# DRV.net
KiCad netlist of a schematic drawn in Altium Designer
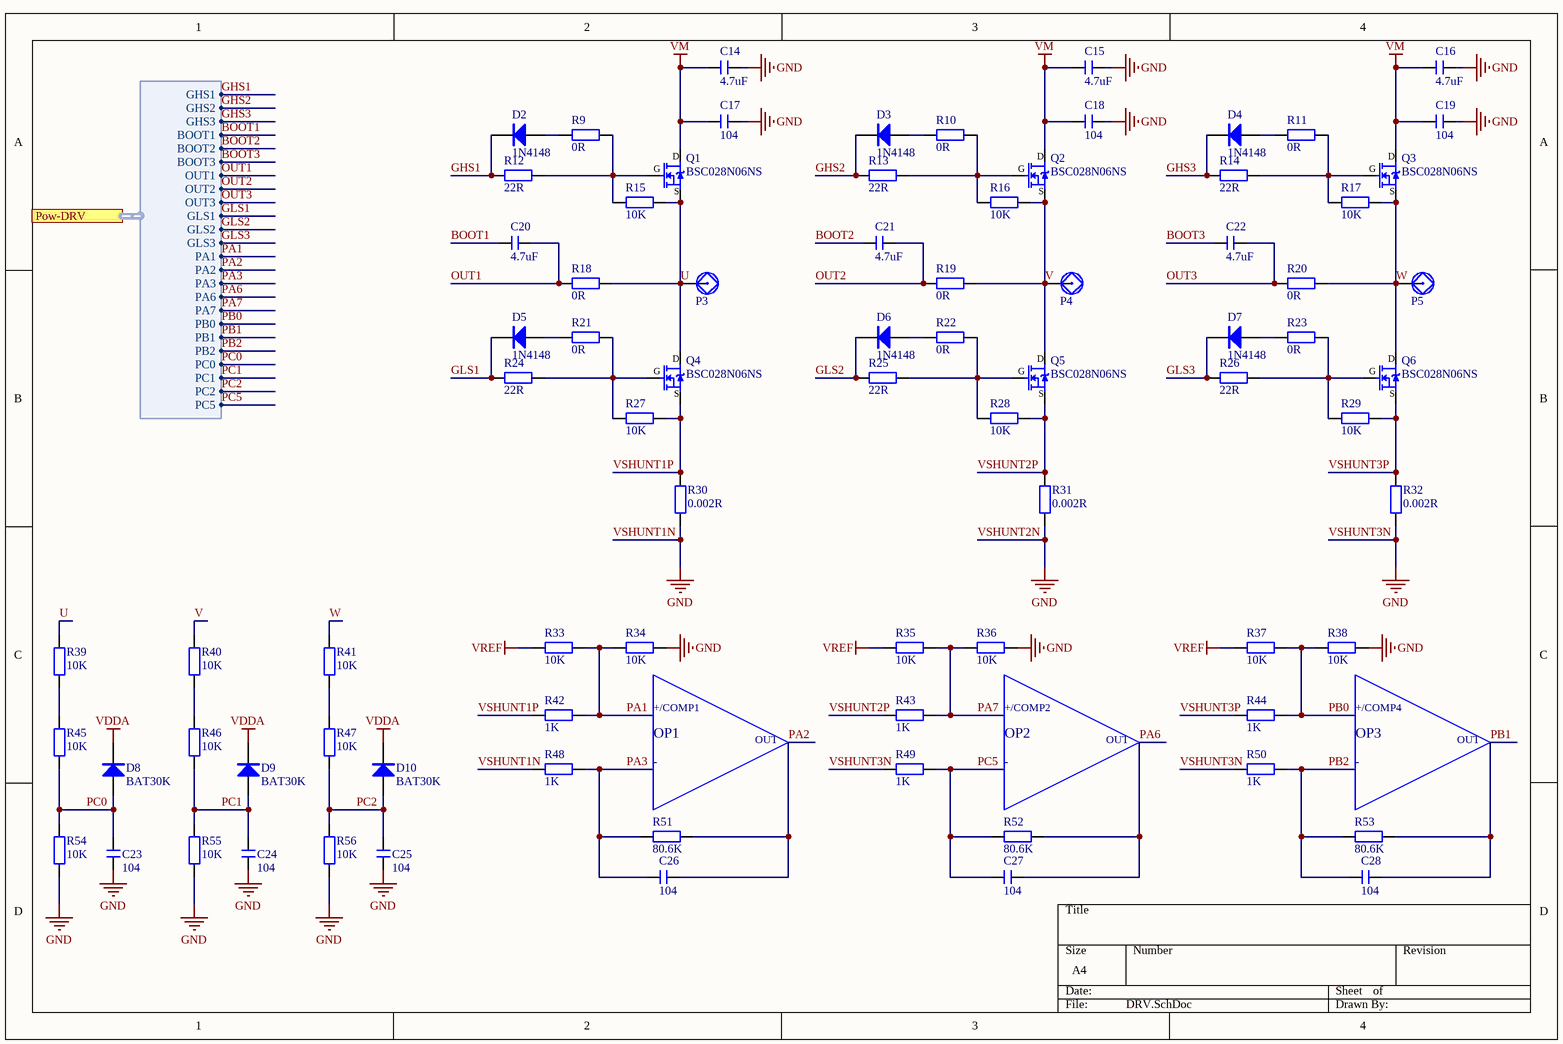
[diagram p0: DRV.SchDoc]

(export (version "E")
  (design (tool "Eeschema 10.0.6"))
  (components
    (comp (ref "C14")
      (value "4.7uF")
      (footprint "C 1206_L")
      (description "无极性贴片电容")
      (fields (field (name "版权归属") "源创客"))
      (libsource (lib "3.1   - 电阻-电容-电感") (part "C"))
    )
    (comp (ref "C15")
      (value "4.7uF")
      (footprint "C 1206_L")
      (description "无极性贴片电容")
      (fields (field (name "版权归属") "源创客"))
      (libsource (lib "3.1   - 电阻-电容-电感") (part "C"))
    )
    (comp (ref "C16")
      (value "4.7uF")
      (footprint "C 1206_L")
      (description "无极性贴片电容")
      (fields (field (name "版权归属") "源创客"))
      (libsource (lib "3.1   - 电阻-电容-电感") (part "C"))
    )
    (comp (ref "C17")
      (value "104")
      (footprint "C 0603_L")
      (description "无极性贴片电容")
      (fields (field (name "版权归属") "源创客"))
      (libsource (lib "3.1   - 电阻-电容-电感") (part "C"))
    )
    (comp (ref "C18")
      (value "104")
      (footprint "C 0603_L")
      (description "无极性贴片电容")
      (fields (field (name "版权归属") "源创客"))
      (libsource (lib "3.1   - 电阻-电容-电感") (part "C"))
    )
    (comp (ref "C19")
      (value "104")
      (footprint "C 0603_L")
      (description "无极性贴片电容")
      (fields (field (name "版权归属") "源创客"))
      (libsource (lib "3.1   - 电阻-电容-电感") (part "C"))
    )
    (comp (ref "C20")
      (value "4.7uF")
      (footprint "C 0805_L")
      (description "无极性贴片电容")
      (fields (field (name "版权归属") "源创客"))
      (libsource (lib "3.1   - 电阻-电容-电感") (part "C"))
    )
    (comp (ref "C21")
      (value "4.7uF")
      (footprint "C 0805_L")
      (description "无极性贴片电容")
      (fields (field (name "版权归属") "源创客"))
      (libsource (lib "3.1   - 电阻-电容-电感") (part "C"))
    )
    (comp (ref "C22")
      (value "4.7uF")
      (footprint "C 0805_L")
      (description "无极性贴片电容")
      (fields (field (name "版权归属") "源创客"))
      (libsource (lib "3.1   - 电阻-电容-电感") (part "C"))
    )
    (comp (ref "C23")
      (value "104")
      (footprint "C 0603_L")
      (description "无极性贴片电容")
      (fields (field (name "版权归属") "源创客"))
      (libsource (lib "3.1   - 电阻-电容-电感") (part "C"))
    )
    (comp (ref "C24")
      (value "104")
      (footprint "C 0603_L")
      (description "无极性贴片电容")
      (fields (field (name "版权归属") "源创客"))
      (libsource (lib "3.1   - 电阻-电容-电感") (part "C"))
    )
    (comp (ref "C25")
      (value "104")
      (footprint "C 0603_L")
      (description "无极性贴片电容")
      (fields (field (name "版权归属") "源创客"))
      (libsource (lib "3.1   - 电阻-电容-电感") (part "C"))
    )
    (comp (ref "C26")
      (value "104")
      (footprint "C 0603_L")
      (description "无极性贴片电容")
      (fields (field (name "版权归属") "源创客"))
      (libsource (lib "3.1   - 电阻-电容-电感") (part "C"))
    )
    (comp (ref "C27")
      (value "104")
      (footprint "C 0603_L")
      (description "无极性贴片电容")
      (fields (field (name "版权归属") "源创客"))
      (libsource (lib "3.1   - 电阻-电容-电感") (part "C"))
    )
    (comp (ref "C28")
      (value "104")
      (footprint "C 0603_L")
      (description "无极性贴片电容")
      (fields (field (name "版权归属") "源创客"))
      (libsource (lib "3.1   - 电阻-电容-电感") (part "C"))
    )
    (comp (ref "D2")
      (value "1N4148")
      (footprint "SOD-323")
      (description "高速开关二极管")
      (fields (field (name "版权归属") "源创客"))
      (libsource (lib "8.1   - 二极管-整流桥") (part "1N4148"))
    )
    (comp (ref "D3")
      (value "1N4148")
      (footprint "SOD-323")
      (description "高速开关二极管")
      (fields (field (name "版权归属") "源创客"))
      (libsource (lib "8.1   - 二极管-整流桥") (part "1N4148"))
    )
    (comp (ref "D4")
      (value "1N4148")
      (footprint "SOD-323")
      (description "高速开关二极管")
      (fields (field (name "版权归属") "源创客"))
      (libsource (lib "8.1   - 二极管-整流桥") (part "1N4148"))
    )
    (comp (ref "D5")
      (value "1N4148")
      (footprint "SOD-323")
      (description "高速开关二极管")
      (fields (field (name "版权归属") "源创客"))
      (libsource (lib "8.1   - 二极管-整流桥") (part "1N4148"))
    )
    (comp (ref "D6")
      (value "1N4148")
      (footprint "SOD-323")
      (description "高速开关二极管")
      (fields (field (name "版权归属") "源创客"))
      (libsource (lib "8.1   - 二极管-整流桥") (part "1N4148"))
    )
    (comp (ref "D7")
      (value "1N4148")
      (footprint "SOD-323")
      (description "高速开关二极管")
      (fields (field (name "版权归属") "源创客"))
      (libsource (lib "8.1   - 二极管-整流桥") (part "1N4148"))
    )
    (comp (ref "D8")
      (value "BAT30K")
      (footprint "SOD-523")
      (description "肖特基二极管")
      (fields (field (name "版权归属") "源创客"))
      (libsource (lib "8.1   - 二极管-整流桥") (part "SS14"))
    )
    (comp (ref "D9")
      (value "BAT30K")
      (footprint "SOD-523")
      (description "肖特基二极管")
      (fields (field (name "版权归属") "源创客"))
      (libsource (lib "8.1   - 二极管-整流桥") (part "SS14"))
    )
    (comp (ref "D10")
      (value "BAT30K")
      (footprint "SOD-523")
      (description "肖特基二极管")
      (fields (field (name "版权归属") "源创客"))
      (libsource (lib "8.1   - 二极管-整流桥") (part "SS14"))
    )
    (comp (ref "P3")
      (value "功率焊盘")
      (footprint "功率焊盘")
      (libsource (lib "STSPIN32G4-Test-board") (part "功率焊盘"))
    )
    (comp (ref "P4")
      (value "功率焊盘")
      (footprint "功率焊盘")
      (libsource (lib "STSPIN32G4-Test-board") (part "功率焊盘"))
    )
    (comp (ref "P5")
      (value "功率焊盘")
      (footprint "功率焊盘")
      (libsource (lib "STSPIN32G4-Test-board") (part "功率焊盘"))
    )
    (comp (ref "Q1")
      (value "BSC028N06NS")
      (footprint "BSC028N06NS")
      (description "N沟场，60V/100A")
      (fields (field (name "版权归属") "源创客"))
      (libsource (lib "STSPIN32G4-Test-board") (part "BSC028N06NS"))
    )
    (comp (ref "Q2")
      (value "BSC028N06NS")
      (footprint "BSC028N06NS")
      (description "N沟场，60V/100A")
      (fields (field (name "版权归属") "源创客"))
      (libsource (lib "STSPIN32G4-Test-board") (part "BSC028N06NS"))
    )
    (comp (ref "Q3")
      (value "BSC028N06NS")
      (footprint "BSC028N06NS")
      (description "N沟场，60V/100A")
      (fields (field (name "版权归属") "源创客"))
      (libsource (lib "STSPIN32G4-Test-board") (part "BSC028N06NS"))
    )
    (comp (ref "Q4")
      (value "BSC028N06NS")
      (footprint "BSC028N06NS")
      (description "N沟场，60V/100A")
      (fields (field (name "版权归属") "源创客"))
      (libsource (lib "STSPIN32G4-Test-board") (part "BSC028N06NS"))
    )
    (comp (ref "Q5")
      (value "BSC028N06NS")
      (footprint "BSC028N06NS")
      (description "N沟场，60V/100A")
      (fields (field (name "版权归属") "源创客"))
      (libsource (lib "STSPIN32G4-Test-board") (part "BSC028N06NS"))
    )
    (comp (ref "Q6")
      (value "BSC028N06NS")
      (footprint "BSC028N06NS")
      (description "N沟场，60V/100A")
      (fields (field (name "版权归属") "源创客"))
      (libsource (lib "STSPIN32G4-Test-board") (part "BSC028N06NS"))
    )
    (comp (ref "R9")
      (value "0R")
      (footprint "R 0603_L")
      (description "贴片电阻")
      (fields (field (name "版权归属") "源创客"))
      (libsource (lib "3.1   - 电阻-电容-电感") (part "R"))
    )
    (comp (ref "R10")
      (value "0R")
      (footprint "R 0603_L")
      (description "贴片电阻")
      (fields (field (name "版权归属") "源创客"))
      (libsource (lib "3.1   - 电阻-电容-电感") (part "R"))
    )
    (comp (ref "R11")
      (value "0R")
      (footprint "R 0603_L")
      (description "贴片电阻")
      (fields (field (name "版权归属") "源创客"))
      (libsource (lib "3.1   - 电阻-电容-电感") (part "R"))
    )
    (comp (ref "R12")
      (value "22R")
      (footprint "R 0603_L")
      (description "贴片电阻")
      (fields (field (name "版权归属") "源创客"))
      (libsource (lib "3.1   - 电阻-电容-电感") (part "R"))
    )
    (comp (ref "R13")
      (value "22R")
      (footprint "R 0603_L")
      (description "贴片电阻")
      (fields (field (name "版权归属") "源创客"))
      (libsource (lib "3.1   - 电阻-电容-电感") (part "R"))
    )
    (comp (ref "R14")
      (value "22R")
      (footprint "R 0603_L")
      (description "贴片电阻")
      (fields (field (name "版权归属") "源创客"))
      (libsource (lib "3.1   - 电阻-电容-电感") (part "R"))
    )
    (comp (ref "R15")
      (value "10K")
      (footprint "R 0603_L")
      (description "贴片电阻")
      (fields (field (name "版权归属") "源创客"))
      (libsource (lib "3.1   - 电阻-电容-电感") (part "R"))
    )
    (comp (ref "R16")
      (value "10K")
      (footprint "R 0603_L")
      (description "贴片电阻")
      (fields (field (name "版权归属") "源创客"))
      (libsource (lib "3.1   - 电阻-电容-电感") (part "R"))
    )
    (comp (ref "R17")
      (value "10K")
      (footprint "R 0603_L")
      (description "贴片电阻")
      (fields (field (name "版权归属") "源创客"))
      (libsource (lib "3.1   - 电阻-电容-电感") (part "R"))
    )
    (comp (ref "R18")
      (value "0R")
      (footprint "R 0603_L")
      (description "贴片电阻")
      (fields (field (name "版权归属") "源创客"))
      (libsource (lib "3.1   - 电阻-电容-电感") (part "R"))
    )
    (comp (ref "R19")
      (value "0R")
      (footprint "R 0603_L")
      (description "贴片电阻")
      (fields (field (name "版权归属") "源创客"))
      (libsource (lib "3.1   - 电阻-电容-电感") (part "R"))
    )
    (comp (ref "R20")
      (value "0R")
      (footprint "R 0603_L")
      (description "贴片电阻")
      (fields (field (name "版权归属") "源创客"))
      (libsource (lib "3.1   - 电阻-电容-电感") (part "R"))
    )
    (comp (ref "R21")
      (value "0R")
      (footprint "R 0603_L")
      (description "贴片电阻")
      (fields (field (name "版权归属") "源创客"))
      (libsource (lib "3.1   - 电阻-电容-电感") (part "R"))
    )
    (comp (ref "R22")
      (value "0R")
      (footprint "R 0603_L")
      (description "贴片电阻")
      (fields (field (name "版权归属") "源创客"))
      (libsource (lib "3.1   - 电阻-电容-电感") (part "R"))
    )
    (comp (ref "R23")
      (value "0R")
      (footprint "R 0603_L")
      (description "贴片电阻")
      (fields (field (name "版权归属") "源创客"))
      (libsource (lib "3.1   - 电阻-电容-电感") (part "R"))
    )
    (comp (ref "R24")
      (value "22R")
      (footprint "R 0603_L")
      (description "贴片电阻")
      (fields (field (name "版权归属") "源创客"))
      (libsource (lib "3.1   - 电阻-电容-电感") (part "R"))
    )
    (comp (ref "R25")
      (value "22R")
      (footprint "R 0603_L")
      (description "贴片电阻")
      (fields (field (name "版权归属") "源创客"))
      (libsource (lib "3.1   - 电阻-电容-电感") (part "R"))
    )
    (comp (ref "R26")
      (value "22R")
      (footprint "R 0603_L")
      (description "贴片电阻")
      (fields (field (name "版权归属") "源创客"))
      (libsource (lib "3.1   - 电阻-电容-电感") (part "R"))
    )
    (comp (ref "R27")
      (value "10K")
      (footprint "R 0603_L")
      (description "贴片电阻")
      (fields (field (name "版权归属") "源创客"))
      (libsource (lib "3.1   - 电阻-电容-电感") (part "R"))
    )
    (comp (ref "R28")
      (value "10K")
      (footprint "R 0603_L")
      (description "贴片电阻")
      (fields (field (name "版权归属") "源创客"))
      (libsource (lib "3.1   - 电阻-电容-电感") (part "R"))
    )
    (comp (ref "R29")
      (value "10K")
      (footprint "R 0603_L")
      (description "贴片电阻")
      (fields (field (name "版权归属") "源创客"))
      (libsource (lib "3.1   - 电阻-电容-电感") (part "R"))
    )
    (comp (ref "R30")
      (value "0.002R")
      (footprint "R 2512_M")
      (description "贴片电阻")
      (fields (field (name "版权归属") "源创客"))
      (libsource (lib "3.1   - 电阻-电容-电感") (part "R"))
    )
    (comp (ref "R31")
      (value "0.002R")
      (footprint "R 2512_M")
      (description "贴片电阻")
      (fields (field (name "版权归属") "源创客"))
      (libsource (lib "3.1   - 电阻-电容-电感") (part "R"))
    )
    (comp (ref "R32")
      (value "0.002R")
      (footprint "R 2512_M")
      (description "贴片电阻")
      (fields (field (name "版权归属") "源创客"))
      (libsource (lib "3.1   - 电阻-电容-电感") (part "R"))
    )
    (comp (ref "R33")
      (value "10K")
      (footprint "R 0603_L")
      (description "贴片电阻")
      (fields (field (name "版权归属") "源创客"))
      (libsource (lib "3.1   - 电阻-电容-电感") (part "R"))
    )
    (comp (ref "R34")
      (value "10K")
      (footprint "R 0603_L")
      (description "贴片电阻")
      (fields (field (name "版权归属") "源创客"))
      (libsource (lib "3.1   - 电阻-电容-电感") (part "R"))
    )
    (comp (ref "R35")
      (value "10K")
      (footprint "R 0603_L")
      (description "贴片电阻")
      (fields (field (name "版权归属") "源创客"))
      (libsource (lib "3.1   - 电阻-电容-电感") (part "R"))
    )
    (comp (ref "R36")
      (value "10K")
      (footprint "R 0603_L")
      (description "贴片电阻")
      (fields (field (name "版权归属") "源创客"))
      (libsource (lib "3.1   - 电阻-电容-电感") (part "R"))
    )
    (comp (ref "R37")
      (value "10K")
      (footprint "R 0603_L")
      (description "贴片电阻")
      (fields (field (name "版权归属") "源创客"))
      (libsource (lib "3.1   - 电阻-电容-电感") (part "R"))
    )
    (comp (ref "R38")
      (value "10K")
      (footprint "R 0603_L")
      (description "贴片电阻")
      (fields (field (name "版权归属") "源创客"))
      (libsource (lib "3.1   - 电阻-电容-电感") (part "R"))
    )
    (comp (ref "R39")
      (value "10K")
      (footprint "R 0603_L")
      (description "贴片电阻")
      (fields (field (name "版权归属") "源创客"))
      (libsource (lib "3.1   - 电阻-电容-电感") (part "R"))
    )
    (comp (ref "R40")
      (value "10K")
      (footprint "R 0603_L")
      (description "贴片电阻")
      (fields (field (name "版权归属") "源创客"))
      (libsource (lib "3.1   - 电阻-电容-电感") (part "R"))
    )
    (comp (ref "R41")
      (value "10K")
      (footprint "R 0603_L")
      (description "贴片电阻")
      (fields (field (name "版权归属") "源创客"))
      (libsource (lib "3.1   - 电阻-电容-电感") (part "R"))
    )
    (comp (ref "R42")
      (value "1K")
      (footprint "R 0603_L")
      (description "贴片电阻")
      (fields (field (name "版权归属") "源创客"))
      (libsource (lib "3.1   - 电阻-电容-电感") (part "R"))
    )
    (comp (ref "R43")
      (value "1K")
      (footprint "R 0603_L")
      (description "贴片电阻")
      (fields (field (name "版权归属") "源创客"))
      (libsource (lib "3.1   - 电阻-电容-电感") (part "R"))
    )
    (comp (ref "R44")
      (value "1K")
      (footprint "R 0603_L")
      (description "贴片电阻")
      (fields (field (name "版权归属") "源创客"))
      (libsource (lib "3.1   - 电阻-电容-电感") (part "R"))
    )
    (comp (ref "R45")
      (value "10K")
      (footprint "R 0603_L")
      (description "贴片电阻")
      (fields (field (name "版权归属") "源创客"))
      (libsource (lib "3.1   - 电阻-电容-电感") (part "R"))
    )
    (comp (ref "R46")
      (value "10K")
      (footprint "R 0603_L")
      (description "贴片电阻")
      (fields (field (name "版权归属") "源创客"))
      (libsource (lib "3.1   - 电阻-电容-电感") (part "R"))
    )
    (comp (ref "R47")
      (value "10K")
      (footprint "R 0603_L")
      (description "贴片电阻")
      (fields (field (name "版权归属") "源创客"))
      (libsource (lib "3.1   - 电阻-电容-电感") (part "R"))
    )
    (comp (ref "R48")
      (value "1K")
      (footprint "R 0603_L")
      (description "贴片电阻")
      (fields (field (name "版权归属") "源创客"))
      (libsource (lib "3.1   - 电阻-电容-电感") (part "R"))
    )
    (comp (ref "R49")
      (value "1K")
      (footprint "R 0603_L")
      (description "贴片电阻")
      (fields (field (name "版权归属") "源创客"))
      (libsource (lib "3.1   - 电阻-电容-电感") (part "R"))
    )
    (comp (ref "R50")
      (value "1K")
      (footprint "R 0603_L")
      (description "贴片电阻")
      (fields (field (name "版权归属") "源创客"))
      (libsource (lib "3.1   - 电阻-电容-电感") (part "R"))
    )
    (comp (ref "R51")
      (value "80.6K")
      (footprint "R 0603_L")
      (description "贴片电阻")
      (fields (field (name "版权归属") "源创客"))
      (libsource (lib "3.1   - 电阻-电容-电感") (part "R"))
    )
    (comp (ref "R52")
      (value "80.6K")
      (footprint "R 0603_L")
      (description "贴片电阻")
      (fields (field (name "版权归属") "源创客"))
      (libsource (lib "3.1   - 电阻-电容-电感") (part "R"))
    )
    (comp (ref "R53")
      (value "80.6K")
      (footprint "R 0603_L")
      (description "贴片电阻")
      (fields (field (name "版权归属") "源创客"))
      (libsource (lib "3.1   - 电阻-电容-电感") (part "R"))
    )
    (comp (ref "R54")
      (value "10K")
      (footprint "R 0603_L")
      (description "贴片电阻")
      (fields (field (name "版权归属") "源创客"))
      (libsource (lib "3.1   - 电阻-电容-电感") (part "R"))
    )
    (comp (ref "R55")
      (value "10K")
      (footprint "R 0603_L")
      (description "贴片电阻")
      (fields (field (name "版权归属") "源创客"))
      (libsource (lib "3.1   - 电阻-电容-电感") (part "R"))
    )
    (comp (ref "R56")
      (value "10K")
      (footprint "R 0603_L")
      (description "贴片电阻")
      (fields (field (name "版权归属") "源创客"))
      (libsource (lib "3.1   - 电阻-电容-电感") (part "R"))
    )
  )
  (nets
    (net (code "2") (name "/BOOT1") (class "Default")
      (node (ref "C20") (pin "2") (pinfunction "2_2") (pintype "passive"))
    )
    (net (code "3") (name "/BOOT2") (class "Default")
      (node (ref "C21") (pin "2") (pinfunction "2_2") (pintype "passive"))
    )
    (net (code "4") (name "/BOOT3") (class "Default")
      (node (ref "C22") (pin "2") (pinfunction "2_2") (pintype "passive"))
    )
    (net (code "5") (name "/GHS1") (class "Default")
      (node (ref "D2") (pin "2") (pinfunction "K_2") (pintype "passive"))
      (node (ref "R12") (pin "2") (pinfunction "2_2") (pintype "passive"))
    )
    (net (code "6") (name "/GHS2") (class "Default")
      (node (ref "D3") (pin "2") (pinfunction "K_2") (pintype "passive"))
      (node (ref "R13") (pin "2") (pinfunction "2_2") (pintype "passive"))
    )
    (net (code "7") (name "/GHS3") (class "Default")
      (node (ref "D4") (pin "2") (pinfunction "K_2") (pintype "passive"))
      (node (ref "R14") (pin "2") (pinfunction "2_2") (pintype "passive"))
    )
    (net (code "8") (name "/GLS1") (class "Default")
      (node (ref "D5") (pin "2") (pinfunction "K_2") (pintype "passive"))
      (node (ref "R24") (pin "2") (pinfunction "2_2") (pintype "passive"))
    )
    (net (code "9") (name "/GLS2") (class "Default")
      (node (ref "D6") (pin "2") (pinfunction "K_2") (pintype "passive"))
      (node (ref "R25") (pin "2") (pinfunction "2_2") (pintype "passive"))
    )
    (net (code "10") (name "/GLS3") (class "Default")
      (node (ref "D7") (pin "2") (pinfunction "K_2") (pintype "passive"))
      (node (ref "R26") (pin "2") (pinfunction "2_2") (pintype "passive"))
    )
    (net (code "11") (name "/OUT1") (class "Default")
      (node (ref "C20") (pin "1") (pinfunction "1_1") (pintype "passive"))
      (node (ref "R18") (pin "2") (pinfunction "2_2") (pintype "passive"))
    )
    (net (code "12") (name "/OUT2") (class "Default")
      (node (ref "C21") (pin "1") (pinfunction "1_1") (pintype "passive"))
      (node (ref "R19") (pin "2") (pinfunction "2_2") (pintype "passive"))
    )
    (net (code "13") (name "/OUT3") (class "Default")
      (node (ref "C22") (pin "1") (pinfunction "1_1") (pintype "passive"))
      (node (ref "R20") (pin "2") (pinfunction "2_2") (pintype "passive"))
    )
    (net (code "14") (name "/PA1") (class "Default")
      (node (ref "R33") (pin "1") (pinfunction "1_1") (pintype "passive"))
      (node (ref "R34") (pin "2") (pinfunction "2_2") (pintype "passive"))
      (node (ref "R42") (pin "1") (pinfunction "1_1") (pintype "passive"))
    )
    (net (code "15") (name "/PA2") (class "Default")
      (node (ref "C26") (pin "1") (pinfunction "1_1") (pintype "passive"))
      (node (ref "R51") (pin "1") (pinfunction "1_1") (pintype "passive"))
    )
    (net (code "16") (name "/PA3") (class "Default")
      (node (ref "C26") (pin "2") (pinfunction "2_2") (pintype "passive"))
      (node (ref "R48") (pin "1") (pinfunction "1_1") (pintype "passive"))
      (node (ref "R51") (pin "2") (pinfunction "2_2") (pintype "passive"))
    )
    (net (code "17") (name "/PA6") (class "Default")
      (node (ref "C27") (pin "1") (pinfunction "1_1") (pintype "passive"))
      (node (ref "R52") (pin "1") (pinfunction "1_1") (pintype "passive"))
    )
    (net (code "18") (name "/PA7") (class "Default")
      (node (ref "R35") (pin "1") (pinfunction "1_1") (pintype "passive"))
      (node (ref "R36") (pin "2") (pinfunction "2_2") (pintype "passive"))
      (node (ref "R43") (pin "1") (pinfunction "1_1") (pintype "passive"))
    )
    (net (code "19") (name "/PB0") (class "Default")
      (node (ref "R37") (pin "1") (pinfunction "1_1") (pintype "passive"))
      (node (ref "R38") (pin "2") (pinfunction "2_2") (pintype "passive"))
      (node (ref "R44") (pin "1") (pinfunction "1_1") (pintype "passive"))
    )
    (net (code "20") (name "/PB1") (class "Default")
      (node (ref "C28") (pin "1") (pinfunction "1_1") (pintype "passive"))
      (node (ref "R53") (pin "1") (pinfunction "1_1") (pintype "passive"))
    )
    (net (code "21") (name "/PB2") (class "Default")
      (node (ref "C28") (pin "2") (pinfunction "2_2") (pintype "passive"))
      (node (ref "R50") (pin "1") (pinfunction "1_1") (pintype "passive"))
      (node (ref "R53") (pin "2") (pinfunction "2_2") (pintype "passive"))
    )
    (net (code "22") (name "/PC0") (class "Default")
      (node (ref "C23") (pin "1") (pinfunction "1_1") (pintype "passive"))
      (node (ref "D8") (pin "1") (pinfunction "A_1") (pintype "passive"))
      (node (ref "R45") (pin "2") (pinfunction "2_2") (pintype "passive"))
      (node (ref "R54") (pin "1") (pinfunction "1_1") (pintype "passive"))
    )
    (net (code "23") (name "/PC1") (class "Default")
      (node (ref "C24") (pin "1") (pinfunction "1_1") (pintype "passive"))
      (node (ref "D9") (pin "1") (pinfunction "A_1") (pintype "passive"))
      (node (ref "R46") (pin "2") (pinfunction "2_2") (pintype "passive"))
      (node (ref "R55") (pin "1") (pinfunction "1_1") (pintype "passive"))
    )
    (net (code "24") (name "/PC2") (class "Default")
      (node (ref "C25") (pin "1") (pinfunction "1_1") (pintype "passive"))
      (node (ref "D10") (pin "1") (pinfunction "A_1") (pintype "passive"))
      (node (ref "R47") (pin "2") (pinfunction "2_2") (pintype "passive"))
      (node (ref "R56") (pin "1") (pinfunction "1_1") (pintype "passive"))
    )
    (net (code "25") (name "/PC5") (class "Default")
      (node (ref "C27") (pin "2") (pinfunction "2_2") (pintype "passive"))
      (node (ref "R49") (pin "1") (pinfunction "1_1") (pintype "passive"))
      (node (ref "R52") (pin "2") (pinfunction "2_2") (pintype "passive"))
    )
    (net (code "26") (name "/U") (class "Default")
      (node (ref "P3") (pin "1") (pinfunction "1_1") (pintype "passive"))
      (node (ref "Q1") (pin "1") (pinfunction "S_1") (pintype "passive"))
      (node (ref "Q4") (pin "3") (pinfunction "D_3") (pintype "passive"))
      (node (ref "R15") (pin "1") (pinfunction "1_1") (pintype "passive"))
      (node (ref "R18") (pin "1") (pinfunction "1_1") (pintype "passive"))
      (node (ref "R39") (pin "1") (pinfunction "1_1") (pintype "passive"))
    )
    (net (code "27") (name "/V") (class "Default")
      (node (ref "P4") (pin "1") (pinfunction "1_1") (pintype "passive"))
      (node (ref "Q2") (pin "1") (pinfunction "S_1") (pintype "passive"))
      (node (ref "Q5") (pin "3") (pinfunction "D_3") (pintype "passive"))
      (node (ref "R16") (pin "1") (pinfunction "1_1") (pintype "passive"))
      (node (ref "R19") (pin "1") (pinfunction "1_1") (pintype "passive"))
      (node (ref "R40") (pin "1") (pinfunction "1_1") (pintype "passive"))
    )
    (net (code "28") (name "/VSHUNT1P") (class "Default")
      (node (ref "Q4") (pin "1") (pinfunction "S_1") (pintype "passive"))
      (node (ref "R27") (pin "1") (pinfunction "1_1") (pintype "passive"))
      (node (ref "R30") (pin "1") (pinfunction "1_1") (pintype "passive"))
      (node (ref "R42") (pin "2") (pinfunction "2_2") (pintype "passive"))
    )
    (net (code "29") (name "/VSHUNT2P") (class "Default")
      (node (ref "Q5") (pin "1") (pinfunction "S_1") (pintype "passive"))
      (node (ref "R28") (pin "1") (pinfunction "1_1") (pintype "passive"))
      (node (ref "R31") (pin "1") (pinfunction "1_1") (pintype "passive"))
      (node (ref "R43") (pin "2") (pinfunction "2_2") (pintype "passive"))
    )
    (net (code "30") (name "/VSHUNT3P") (class "Default")
      (node (ref "Q6") (pin "1") (pinfunction "S_1") (pintype "passive"))
      (node (ref "R29") (pin "1") (pinfunction "1_1") (pintype "passive"))
      (node (ref "R32") (pin "1") (pinfunction "1_1") (pintype "passive"))
      (node (ref "R44") (pin "2") (pinfunction "2_2") (pintype "passive"))
    )
    (net (code "31") (name "/W") (class "Default")
      (node (ref "P5") (pin "1") (pinfunction "1_1") (pintype "passive"))
      (node (ref "Q3") (pin "1") (pinfunction "S_1") (pintype "passive"))
      (node (ref "Q6") (pin "3") (pinfunction "D_3") (pintype "passive"))
      (node (ref "R17") (pin "1") (pinfunction "1_1") (pintype "passive"))
      (node (ref "R20") (pin "1") (pinfunction "1_1") (pintype "passive"))
      (node (ref "R41") (pin "1") (pinfunction "1_1") (pintype "passive"))
    )
    (net (code "33") (name "GND") (class "Default")
      (node (ref "C14") (pin "1") (pinfunction "1_1") (pintype "passive"))
      (node (ref "C15") (pin "1") (pinfunction "1_1") (pintype "passive"))
      (node (ref "C16") (pin "1") (pinfunction "1_1") (pintype "passive"))
      (node (ref "C17") (pin "1") (pinfunction "1_1") (pintype "passive"))
      (node (ref "C18") (pin "1") (pinfunction "1_1") (pintype "passive"))
      (node (ref "C19") (pin "1") (pinfunction "1_1") (pintype "passive"))
      (node (ref "C23") (pin "2") (pinfunction "2_2") (pintype "passive"))
      (node (ref "C24") (pin "2") (pinfunction "2_2") (pintype "passive"))
      (node (ref "C25") (pin "2") (pinfunction "2_2") (pintype "passive"))
      (node (ref "R30") (pin "2") (pinfunction "2_2") (pintype "passive"))
      (node (ref "R31") (pin "2") (pinfunction "2_2") (pintype "passive"))
      (node (ref "R32") (pin "2") (pinfunction "2_2") (pintype "passive"))
      (node (ref "R34") (pin "1") (pinfunction "1_1") (pintype "passive"))
      (node (ref "R36") (pin "1") (pinfunction "1_1") (pintype "passive"))
      (node (ref "R38") (pin "1") (pinfunction "1_1") (pintype "passive"))
      (node (ref "R48") (pin "2") (pinfunction "2_2") (pintype "passive"))
      (node (ref "R49") (pin "2") (pinfunction "2_2") (pintype "passive"))
      (node (ref "R50") (pin "2") (pinfunction "2_2") (pintype "passive"))
      (node (ref "R54") (pin "2") (pinfunction "2_2") (pintype "passive"))
      (node (ref "R55") (pin "2") (pinfunction "2_2") (pintype "passive"))
      (node (ref "R56") (pin "2") (pinfunction "2_2") (pintype "passive"))
    )
    (net (code "34") (name "Net-(D2-A)") (class "Default")
      (node (ref "D2") (pin "1") (pinfunction "A_1") (pintype "passive"))
      (node (ref "R9") (pin "2") (pinfunction "2_2") (pintype "passive"))
    )
    (net (code "35") (name "Net-(D3-A)") (class "Default")
      (node (ref "D3") (pin "1") (pinfunction "A_1") (pintype "passive"))
      (node (ref "R10") (pin "2") (pinfunction "2_2") (pintype "passive"))
    )
    (net (code "36") (name "Net-(D4-A)") (class "Default")
      (node (ref "D4") (pin "1") (pinfunction "A_1") (pintype "passive"))
      (node (ref "R11") (pin "2") (pinfunction "2_2") (pintype "passive"))
    )
    (net (code "37") (name "Net-(D5-A)") (class "Default")
      (node (ref "D5") (pin "1") (pinfunction "A_1") (pintype "passive"))
      (node (ref "R21") (pin "2") (pinfunction "2_2") (pintype "passive"))
    )
    (net (code "38") (name "Net-(D6-A)") (class "Default")
      (node (ref "D6") (pin "1") (pinfunction "A_1") (pintype "passive"))
      (node (ref "R22") (pin "2") (pinfunction "2_2") (pintype "passive"))
    )
    (net (code "39") (name "Net-(D7-A)") (class "Default")
      (node (ref "D7") (pin "1") (pinfunction "A_1") (pintype "passive"))
      (node (ref "R23") (pin "2") (pinfunction "2_2") (pintype "passive"))
    )
    (net (code "40") (name "Net-(Q1-G)") (class "Default")
      (node (ref "Q1") (pin "2") (pinfunction "G_2") (pintype "passive"))
      (node (ref "R12") (pin "1") (pinfunction "1_1") (pintype "passive"))
      (node (ref "R15") (pin "2") (pinfunction "2_2") (pintype "passive"))
      (node (ref "R9") (pin "1") (pinfunction "1_1") (pintype "passive"))
    )
    (net (code "41") (name "Net-(Q2-G)") (class "Default")
      (node (ref "Q2") (pin "2") (pinfunction "G_2") (pintype "passive"))
      (node (ref "R10") (pin "1") (pinfunction "1_1") (pintype "passive"))
      (node (ref "R13") (pin "1") (pinfunction "1_1") (pintype "passive"))
      (node (ref "R16") (pin "2") (pinfunction "2_2") (pintype "passive"))
    )
    (net (code "42") (name "Net-(Q3-G)") (class "Default")
      (node (ref "Q3") (pin "2") (pinfunction "G_2") (pintype "passive"))
      (node (ref "R11") (pin "1") (pinfunction "1_1") (pintype "passive"))
      (node (ref "R14") (pin "1") (pinfunction "1_1") (pintype "passive"))
      (node (ref "R17") (pin "2") (pinfunction "2_2") (pintype "passive"))
    )
    (net (code "43") (name "Net-(Q4-G)") (class "Default")
      (node (ref "Q4") (pin "2") (pinfunction "G_2") (pintype "passive"))
      (node (ref "R21") (pin "1") (pinfunction "1_1") (pintype "passive"))
      (node (ref "R24") (pin "1") (pinfunction "1_1") (pintype "passive"))
      (node (ref "R27") (pin "2") (pinfunction "2_2") (pintype "passive"))
    )
    (net (code "44") (name "Net-(Q5-G)") (class "Default")
      (node (ref "Q5") (pin "2") (pinfunction "G_2") (pintype "passive"))
      (node (ref "R22") (pin "1") (pinfunction "1_1") (pintype "passive"))
      (node (ref "R25") (pin "1") (pinfunction "1_1") (pintype "passive"))
      (node (ref "R28") (pin "2") (pinfunction "2_2") (pintype "passive"))
    )
    (net (code "45") (name "Net-(Q6-G)") (class "Default")
      (node (ref "Q6") (pin "2") (pinfunction "G_2") (pintype "passive"))
      (node (ref "R23") (pin "1") (pinfunction "1_1") (pintype "passive"))
      (node (ref "R26") (pin "1") (pinfunction "1_1") (pintype "passive"))
      (node (ref "R29") (pin "2") (pinfunction "2_2") (pintype "passive"))
    )
    (net (code "46") (name "Net-(R39-Pad2)") (class "Default")
      (node (ref "R39") (pin "2") (pinfunction "2_2") (pintype "passive"))
      (node (ref "R45") (pin "1") (pinfunction "1_1") (pintype "passive"))
    )
    (net (code "47") (name "Net-(R40-Pad2)") (class "Default")
      (node (ref "R40") (pin "2") (pinfunction "2_2") (pintype "passive"))
      (node (ref "R46") (pin "1") (pinfunction "1_1") (pintype "passive"))
    )
    (net (code "48") (name "Net-(R41-Pad2)") (class "Default")
      (node (ref "R41") (pin "2") (pinfunction "2_2") (pintype "passive"))
      (node (ref "R47") (pin "1") (pinfunction "1_1") (pintype "passive"))
    )
    (net (code "49") (name "VDDA") (class "Default")
      (node (ref "D10") (pin "2") (pinfunction "K_2") (pintype "passive"))
      (node (ref "D8") (pin "2") (pinfunction "K_2") (pintype "passive"))
      (node (ref "D9") (pin "2") (pinfunction "K_2") (pintype "passive"))
    )
    (net (code "50") (name "VM") (class "Default")
      (node (ref "C14") (pin "2") (pinfunction "2_2") (pintype "passive"))
      (node (ref "C15") (pin "2") (pinfunction "2_2") (pintype "passive"))
      (node (ref "C16") (pin "2") (pinfunction "2_2") (pintype "passive"))
      (node (ref "C17") (pin "2") (pinfunction "2_2") (pintype "passive"))
      (node (ref "C18") (pin "2") (pinfunction "2_2") (pintype "passive"))
      (node (ref "C19") (pin "2") (pinfunction "2_2") (pintype "passive"))
      (node (ref "Q1") (pin "3") (pinfunction "D_3") (pintype "passive"))
      (node (ref "Q2") (pin "3") (pinfunction "D_3") (pintype "passive"))
      (node (ref "Q3") (pin "3") (pinfunction "D_3") (pintype "passive"))
    )
    (net (code "51") (name "VREF") (class "Default")
      (node (ref "R33") (pin "2") (pinfunction "2_2") (pintype "passive"))
      (node (ref "R35") (pin "2") (pinfunction "2_2") (pintype "passive"))
      (node (ref "R37") (pin "2") (pinfunction "2_2") (pintype "passive"))
    )
  )
)
